# headstage-64-coax-adapter.net
KiCad netlist of a schematic drawn in EAGLE
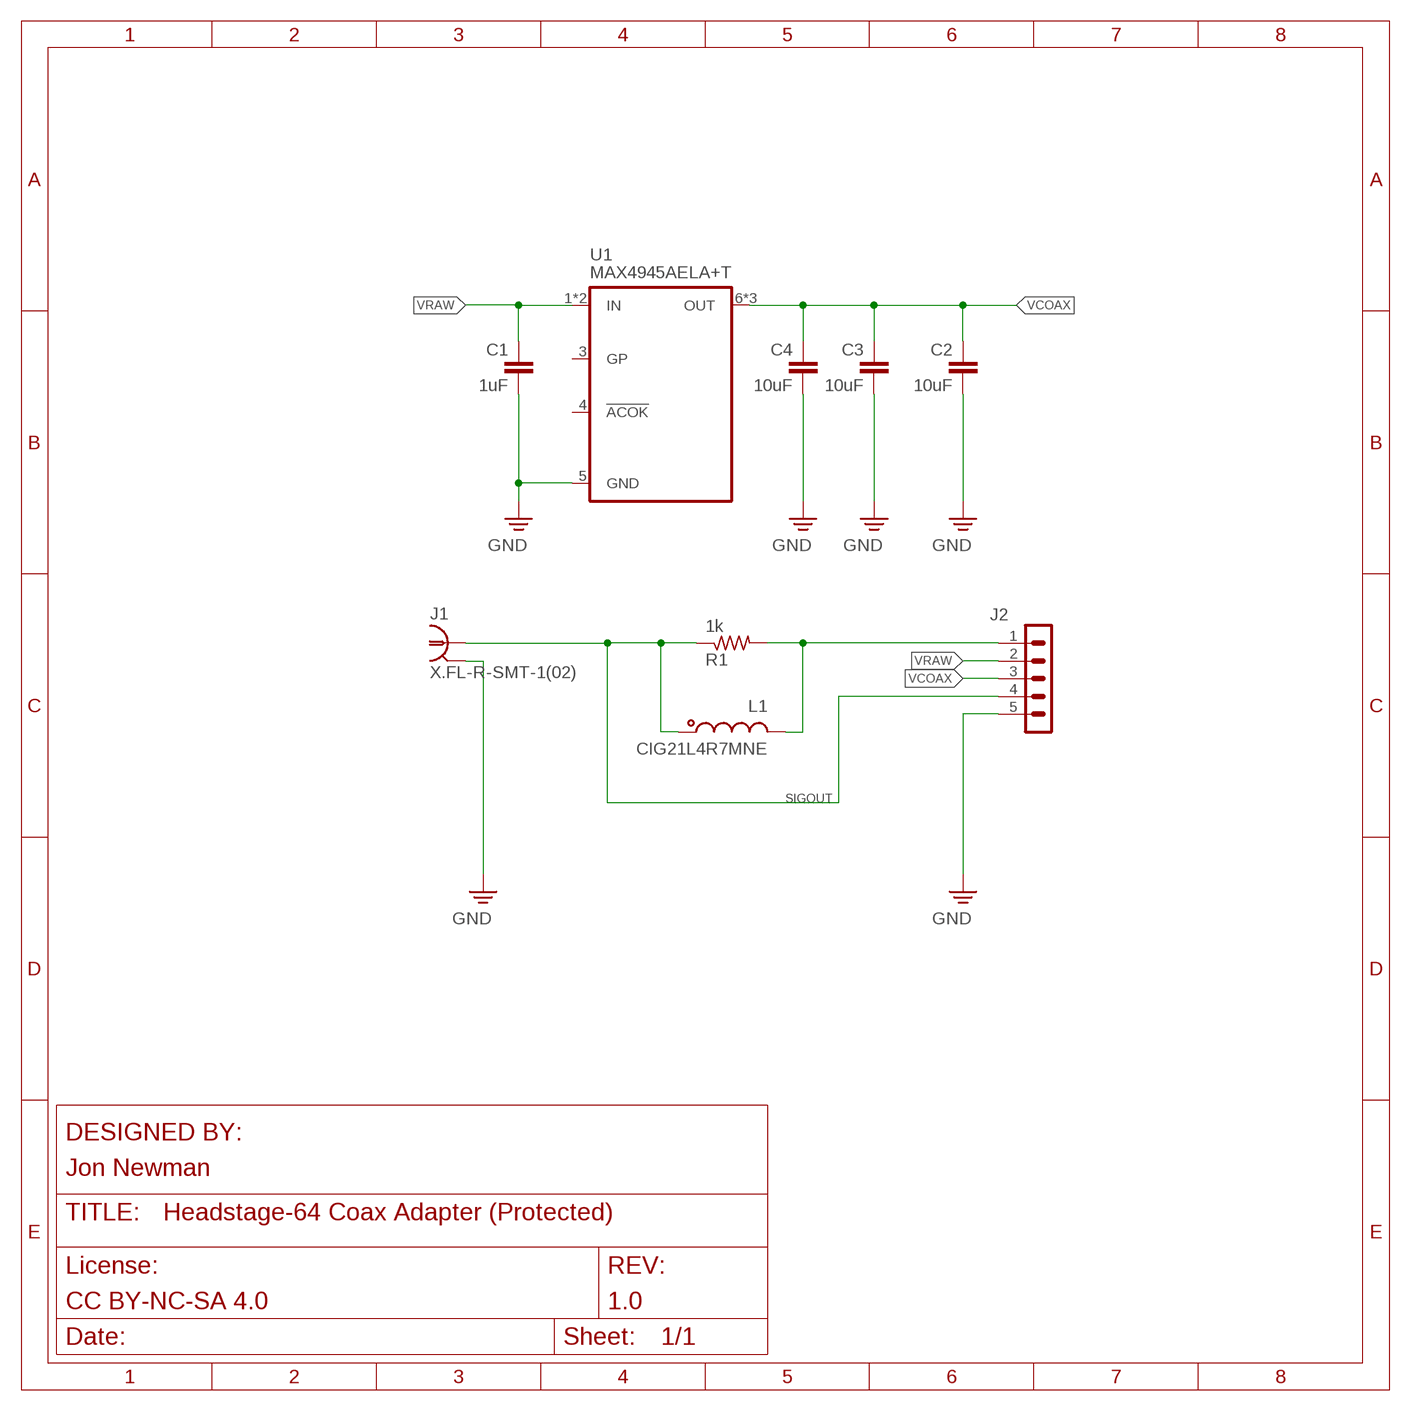
[diagram p0: schematic, sheet 1]

(export (version "E")
  (design (tool "Eeschema 10.0.6"))
  (components
    (comp (ref "C1")
      (value "1uF")
      (footprint "eagle-import:0402T")
      (fields (field (name "PARTNO") "CL05A475MO5NUNC"))
      (libsource (lib "eagle-import") (part "C_0402T"))
    )
    (comp (ref "C2")
      (value "10uF")
      (footprint "eagle-import:0402T")
      (fields (field (name "PARTNO") "CL05A475MO5NUNC"))
      (libsource (lib "eagle-import") (part "C_0402T"))
    )
    (comp (ref "C3")
      (value "10uF")
      (footprint "eagle-import:0603T")
      (fields (field (name "PARTNO") "CL05A475MO5NUNC"))
      (libsource (lib "eagle-import") (part "C_0603T"))
    )
    (comp (ref "C4")
      (value "10uF")
      (footprint "eagle-import:0603T")
      (fields (field (name "PARTNO") "CL05A475MO5NUNC"))
      (libsource (lib "eagle-import") (part "C_0603T"))
    )
    (comp (ref "J1")
      (value "X.FL-R-SMT-1(02)")
      (footprint "eagle-import:X_FL_R_SMT_1(02)")
      (libsource (lib "eagle-import") (part "COAX_XFL"))
    )
    (comp (ref "J2")
      (value "PINHD-1X5_HEADSTAGE-64-REV1.4-DAUGHTER-CARD-CASTELLATED")
      (footprint "eagle-import:HEADSTAGE-64-REV1.4-DAUGHTER-CARD-CASTELLATED")
      (libsource (lib "eagle-import") (part "PINHD-1X5_HEADSTAGE-64-REV1.4-DAUGHTER-CARD-CASTELLATED"))
    )
    (comp (ref "L1")
      (value "CIG21L4R7MNE")
      (footprint "eagle-import:0805T")
      (libsource (lib "eagle-import") (part "L_0805T"))
    )
    (comp (ref "R1")
      (value "1k")
      (footprint "eagle-import:0201T")
      (libsource (lib "eagle-import") (part "R_0201T"))
    )
    (comp (ref "U1")
      (value "MAX4945AELA+T")
      (footprint "eagle-import:UDFN8-2X2")
      (libsource (lib "eagle-import") (part "MAX494X"))
    )
  )
  (nets
    (net (code "1") (name "/SIGOUT") (class "Default")
      (node (ref "J1") (pin "P$1") (pinfunction "1_P$1") (pintype "passive"))
      (node (ref "J2") (pin "4") (pinfunction "4_4") (pintype "passive"))
      (node (ref "L1") (pin "1") (pinfunction "1_1") (pintype "passive"))
      (node (ref "R1") (pin "1") (pinfunction "1_1") (pintype "passive"))
    )
    (net (code "2") (name "GND") (class "Default")
      (node (ref "C1") (pin "2") (pinfunction "2_2") (pintype "passive"))
      (node (ref "C2") (pin "2") (pinfunction "2_2") (pintype "passive"))
      (node (ref "C3") (pin "2") (pinfunction "2_2") (pintype "passive"))
      (node (ref "C4") (pin "2") (pinfunction "2_2") (pintype "passive"))
      (node (ref "J1") (pin "P$2") (pinfunction "2_P$2") (pintype "passive"))
      (node (ref "J1") (pin "P$3") (pinfunction "2_P$3") (pintype "passive"))
      (node (ref "J1") (pin "P$4") (pinfunction "2_P$4") (pintype "passive"))
      (node (ref "J2") (pin "5") (pinfunction "5_5") (pintype "passive"))
      (node (ref "U1") (pin "5") (pinfunction "GND_5") (pintype "power_in"))
    )
    (net (code "3") (name "Net-(J2-Pad1)") (class "Default")
      (node (ref "J2") (pin "1") (pinfunction "1_1") (pintype "passive"))
      (node (ref "L1") (pin "2") (pinfunction "2_2") (pintype "passive"))
      (node (ref "R1") (pin "2") (pinfunction "2_2") (pintype "passive"))
    )
    (net (code "4") (name "VCOAX") (class "Default")
      (node (ref "C2") (pin "1") (pinfunction "1_1") (pintype "passive"))
      (node (ref "C3") (pin "1") (pinfunction "1_1") (pintype "passive"))
      (node (ref "C4") (pin "1") (pinfunction "1_1") (pintype "passive"))
      (node (ref "J2") (pin "3") (pinfunction "3_3") (pintype "passive"))
      (node (ref "U1") (pin "6") (pinfunction "OUT_6") (pintype "output"))
      (node (ref "U1") (pin "7") (pinfunction "OUT_7") (pintype "output"))
      (node (ref "U1") (pin "8") (pinfunction "OUT_8") (pintype "output"))
    )
    (net (code "5") (name "VRAW") (class "Default")
      (node (ref "C1") (pin "1") (pinfunction "1_1") (pintype "passive"))
      (node (ref "J2") (pin "2") (pinfunction "2_2") (pintype "passive"))
      (node (ref "U1") (pin "1") (pinfunction "IN_1") (pintype "power_in"))
      (node (ref "U1") (pin "2") (pinfunction "IN_2") (pintype "power_in"))
    )
    (net (code "6") (name "unconnected-(U1-GP-Pad3)") (class "Default")
      (node (ref "U1") (pin "3") (pinfunction "GP_3") (pintype "output"))
    )
    (net (code "7") (name "unconnected-(U1-~{ACOK}-Pad4)") (class "Default")
      (node (ref "U1") (pin "4") (pinfunction "~{ACOK}_4") (pintype "open_collector"))
    )
  )
)
